# power.net
KiCad netlist of a schematic drawn in Altium Designer
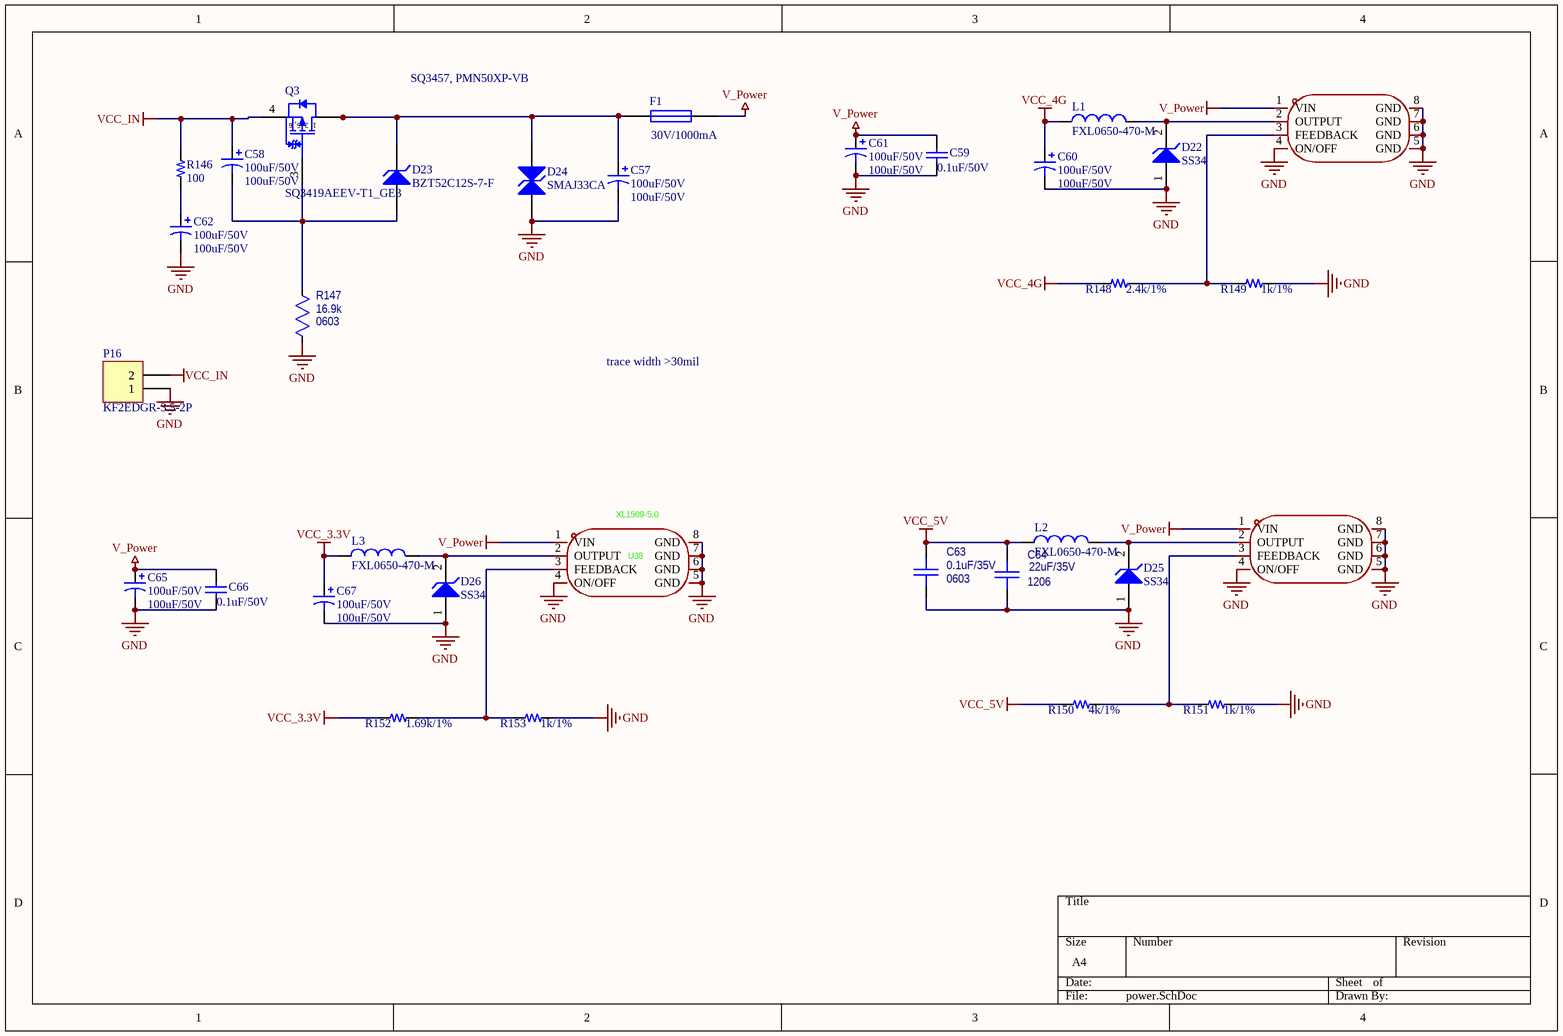
[diagram p0: power.SchDoc]

(export (version "E")
  (design (tool "Eeschema 10.0.6"))
  (components
    (comp (ref "C57")
      (value "100uF/50V")
      (footprint "CAP-SMD_BD6.3-L6.5-W6.5-LS7.0-FD:CAP-SMD_BD6.3-L6.5-W6.5-LS7.0-FD")
      (description "Polarized Capacitor (Surface Mount)")
      (fields (field (name "ALTIUM_VALUE") "100uF/50V"))
      (libsource (lib "Miscellaneous Devices") (part "Cap Pol3"))
    )
    (comp (ref "C58")
      (value "100uF/50V")
      (footprint "CAP-SMD_BD6.3-L6.5-W6.5-LS7.0-FD:CAP-SMD_BD6.3-L6.5-W6.5-LS7.0-FD")
      (description "Polarized Capacitor (Surface Mount)")
      (fields (field (name "ALTIUM_VALUE") "100uF/50V"))
      (libsource (lib "Miscellaneous Devices") (part "Cap Pol3"))
    )
    (comp (ref "C59")
      (value "0.1uF/50V")
      (footprint "0603C")
      (description "Capacitor")
      (libsource (lib "Miscellaneous Devices") (part "Cap"))
    )
    (comp (ref "C60")
      (value "100uF/50V")
      (footprint "CAP-SMD_BD6.3-L6.5-W6.5-LS7.0-FD:CAP-SMD_BD6.3-L6.5-W6.5-LS7.0-FD")
      (description "Polarized Capacitor (Surface Mount)")
      (fields (field (name "ALTIUM_VALUE") "100uF/50V"))
      (libsource (lib "Miscellaneous Devices") (part "Cap Pol3"))
    )
    (comp (ref "C61")
      (value "100uF/50V")
      (footprint "CAP-SMD_BD6.3-L6.5-W6.5-LS7.0-FD:CAP-SMD_BD6.3-L6.5-W6.5-LS7.0-FD")
      (description "Polarized Capacitor (Surface Mount)")
      (fields (field (name "ALTIUM_VALUE") "100uF/50V"))
      (libsource (lib "Miscellaneous Devices") (part "Cap Pol3"))
    )
    (comp (ref "C62")
      (value "100uF/50V")
      (footprint "CAP-SMD_BD6.3-L6.5-W6.5-LS7.0-FD:CAP-SMD_BD6.3-L6.5-W6.5-LS7.0-FD")
      (description "Polarized Capacitor (Surface Mount)")
      (fields (field (name "ALTIUM_VALUE") "100uF/50V"))
      (libsource (lib "Miscellaneous Devices") (part "Cap Pol3"))
    )
    (comp (ref "C63")
      (value "0.1uF/35V")
      (footprint "CAPC3216X156N_1206")
      (fields (field (name "PARTNUMBER") "GRM31CR61E476ME44L") (field (name "PACKAGE") "0603"))
      (libsource (lib "Karl") (part "Capacitor_1206"))
    )
    (comp (ref "C64")
      (value "22uF/35V")
      (footprint "CAPC3216X156N_1206")
      (fields (field (name "PARTNUMBER") "GRM31CR61E476ME44L") (field (name "PACKAGE") "1206"))
      (libsource (lib "Karl") (part "Capacitor_1206"))
    )
    (comp (ref "C65")
      (value "100uF/50V")
      (footprint "CAP-SMD_BD6.3-L6.5-W6.5-LS7.0-FD:CAP-SMD_BD6.3-L6.5-W6.5-LS7.0-FD")
      (description "Polarized Capacitor (Surface Mount)")
      (fields (field (name "ALTIUM_VALUE") "100uF/50V"))
      (libsource (lib "Miscellaneous Devices") (part "Cap Pol3"))
    )
    (comp (ref "C66")
      (value "0.1uF/50V")
      (footprint "0603C")
      (description "Capacitor")
      (libsource (lib "Miscellaneous Devices") (part "Cap"))
    )
    (comp (ref "C67")
      (value "100uF/50V")
      (footprint "CAP-SMD_BD6.3-L6.5-W6.5-LS7.0-FD:CAP-SMD_BD6.3-L6.5-W6.5-LS7.0-FD")
      (description "Polarized Capacitor (Surface Mount)")
      (fields (field (name "ALTIUM_VALUE") "100uF/50V"))
      (libsource (lib "Miscellaneous Devices") (part "Cap Pol3"))
    )
    (comp (ref "D22")
      (value "SS34")
      (footprint "SMA")
      (description "Schottky Barrier Rectifier, 40 V, 2-Pin SMA-FL, Pb-Free, Tape and Reel")
      (fields (field (name "PARTNUMBER") "B540C-13-F"))
      (libsource (lib "Bogen") (part "FSV340AF"))
    )
    (comp (ref "D23")
      (value "BZT52C12S-7-F")
      (footprint "DIOD-SOD323-2_V")
      (fields (field (name "PARTNUMBER") "BZT52C12S"))
      (libsource (lib "Bogen") (part "BZT52C12S-7-F"))
    )
    (comp (ref "D24")
      (value "SMAJ33CA")
      (footprint "LFUS-DO-214AC-A-2_N")
      (libsource (lib "Bogen") (part "SMAJ12CA"))
    )
    (comp (ref "D25")
      (value "SS34")
      (footprint "SMA")
      (description "Schottky Barrier Rectifier, 40 V, 2-Pin SMA-FL, Pb-Free, Tape and Reel")
      (fields (field (name "PARTNUMBER") "B540C-13-F"))
      (libsource (lib "Bogen") (part "FSV340AF"))
    )
    (comp (ref "D26")
      (value "SS34")
      (footprint "SMA")
      (description "Schottky Barrier Rectifier, 40 V, 2-Pin SMA-FL, Pb-Free, Tape and Reel")
      (fields (field (name "PARTNUMBER") "B540C-13-F"))
      (libsource (lib "Bogen") (part "FSV340AF"))
    )
    (comp (ref "F1")
      (value "30V/1000mA")
      (footprint "RESC3216X070N_1206")
      (fields (field (name "PARTNUMBER") "BSMD1206-050-30V"))
      (libsource (lib "Miscellaneous Devices") (part "Fuse 1"))
    )
    (comp (ref "L1")
      (value "FXL0650-470-M")
      (footprint "PULS-BDCD00252012_V")
      (fields (field (name "PARTNUMBER") "BDCD002520122R2MS1"))
      (libsource (lib "Bogen") (part "BDCD002520122R2MS1"))
    )
    (comp (ref "L2")
      (value "FXL0650-470-M")
      (footprint "PULS-BDCD00252012_V")
      (fields (field (name "PARTNUMBER") "BDCD002520122R2MS1"))
      (libsource (lib "Bogen") (part "BDCD002520122R2MS1"))
    )
    (comp (ref "L3")
      (value "FXL0650-470-M")
      (footprint "PULS-BDCD00252012_V")
      (fields (field (name "PARTNUMBER") "BDCD002520122R2MS1"))
      (libsource (lib "Bogen") (part "BDCD002520122R2MS1"))
    )
    (comp (ref "P16")
      (value "KF2EDGR-3.5-2P")
      (footprint "CONN-TH_P3.50_KF2EDGR-3.5-2P:CONN-TH_P3.50_KF2EDGR-3.5-2P")
      (description "Header, 2-Pin")
      (libsource (lib "Miscellaneous Connectors") (part "Header 2"))
    )
    (comp (ref "Q3")
      (value "SQ3419AEEV-T1_GE3")
      (footprint "VISH-TSOP-6_V")
      (fields (field (name "PARTNUMBER") "PMN50XP-VB"))
      (libsource (lib "Bogen") (part "SQ3419AEEV-T1_GE3"))
    )
    (comp (ref "R146")
      (value "100")
      (footprint "RESC1608X055N_0603")
      (fields (field (name "PARTNUMBER") "RC0603FR-071KL"))
      (libsource (lib "JRJ_1") (part "R"))
    )
    (comp (ref "R147")
      (value "16.9k")
      (footprint "RESC1608X055N_0603")
      (fields
        (field (name "PARTNUMBER") "FRC0603F1692TS")
        (field (name "PACKAGE") "0603")
        (field (name "Comment") "16.9k/1%")
      )
      (libsource (lib "Karl") (part "Resistor_0603"))
    )
    (comp (ref "R148")
      (value "2.4k/1%")
      (footprint "RESC1608X055N_0603")
      (fields (field (name "PARTNUMBER") "RC0603FR-071KL"))
      (libsource (lib "JRJ_1") (part "R"))
    )
    (comp (ref "R149")
      (value "1k/1%")
      (footprint "RESC1608X055N_0603")
      (fields (field (name "PARTNUMBER") "RC0603FR-071KL"))
      (libsource (lib "JRJ_1") (part "R"))
    )
    (comp (ref "R150")
      (value "4k/1%")
      (footprint "RESC1608X055N_0603")
      (fields (field (name "PARTNUMBER") "RC0603FR-071KL"))
      (libsource (lib "JRJ_1") (part "R"))
    )
    (comp (ref "R151")
      (value "1k/1%")
      (footprint "RESC1608X055N_0603")
      (fields (field (name "PARTNUMBER") "RC0603FR-071KL"))
      (libsource (lib "JRJ_1") (part "R"))
    )
    (comp (ref "R152")
      (value "1.69k/1%")
      (footprint "RESC1608X055N_0603")
      (fields (field (name "PARTNUMBER") "RC0603FR-071KL"))
      (libsource (lib "JRJ_1") (part "R"))
    )
    (comp (ref "R153")
      (value "1k/1%")
      (footprint "RESC1608X055N_0603")
      (fields (field (name "PARTNUMBER") "RC0603FR-071KL"))
      (libsource (lib "JRJ_1") (part "R"))
    )
    (comp (ref "U36")
      (value "XL1509-5.0")
      (footprint "so-8")
      (libsource (lib "altium-import") (part "root_0_XL1509-5.0_"))
    )
    (comp (ref "U37")
      (value "XL1509-5.0")
      (footprint "so-8")
      (libsource (lib "altium-import") (part "root_0_XL1509-5.0_"))
    )
    (comp (ref "U38")
      (value "XL1509-5.0")
      (footprint "so-8")
      (libsource (lib "altium-import") (part "root_0_XL1509-5.0_"))
    )
  )
  (nets
    (net (code "1") (name "GND") (class "Default")
      (node (ref "C57") (pin "2") (pinfunction "2_2") (pintype "passive"))
      (node (ref "C59") (pin "1") (pinfunction "1_1") (pintype "passive"))
      (node (ref "C60") (pin "2") (pinfunction "2_2") (pintype "passive"))
      (node (ref "C61") (pin "2") (pinfunction "2_2") (pintype "passive"))
      (node (ref "C62") (pin "2") (pinfunction "2_2") (pintype "passive"))
      (node (ref "C63") (pin "2") (pinfunction "2_2") (pintype "passive"))
      (node (ref "C64") (pin "2") (pinfunction "2_2") (pintype "passive"))
      (node (ref "C65") (pin "2") (pinfunction "2_2") (pintype "passive"))
      (node (ref "C66") (pin "1") (pinfunction "1_1") (pintype "passive"))
      (node (ref "C67") (pin "2") (pinfunction "2_2") (pintype "passive"))
      (node (ref "D22") (pin "1") (pinfunction "A_1") (pintype "passive"))
      (node (ref "D24") (pin "1") (pinfunction "A_1") (pintype "passive"))
      (node (ref "D25") (pin "1") (pinfunction "A_1") (pintype "passive"))
      (node (ref "D26") (pin "1") (pinfunction "A_1") (pintype "passive"))
      (node (ref "P16") (pin "1") (pinfunction "1_1") (pintype "passive"))
      (node (ref "R147") (pin "1") (pinfunction "1_1") (pintype "passive"))
      (node (ref "R149") (pin "1") (pintype "passive"))
      (node (ref "R151") (pin "1") (pintype "passive"))
      (node (ref "R153") (pin "1") (pintype "passive"))
      (node (ref "U36") (pin "4") (pinfunction "ON/OFF_4") (pintype "passive"))
      (node (ref "U36") (pin "5") (pinfunction "GND_5") (pintype "passive"))
      (node (ref "U36") (pin "6") (pinfunction "GND_6") (pintype "passive"))
      (node (ref "U36") (pin "7") (pinfunction "GND_7") (pintype "passive"))
      (node (ref "U36") (pin "8") (pinfunction "GND_8") (pintype "passive"))
      (node (ref "U37") (pin "4") (pinfunction "ON/OFF_4") (pintype "passive"))
      (node (ref "U37") (pin "5") (pinfunction "GND_5") (pintype "passive"))
      (node (ref "U37") (pin "6") (pinfunction "GND_6") (pintype "passive"))
      (node (ref "U37") (pin "7") (pinfunction "GND_7") (pintype "passive"))
      (node (ref "U37") (pin "8") (pinfunction "GND_8") (pintype "passive"))
      (node (ref "U38") (pin "4") (pinfunction "ON/OFF_4") (pintype "passive"))
      (node (ref "U38") (pin "5") (pinfunction "GND_5") (pintype "passive"))
      (node (ref "U38") (pin "6") (pinfunction "GND_6") (pintype "passive"))
      (node (ref "U38") (pin "7") (pinfunction "GND_7") (pintype "passive"))
      (node (ref "U38") (pin "8") (pinfunction "GND_8") (pintype "passive"))
    )
    (net (code "2") (name "Net-(C62-Pad1)") (class "Default")
      (node (ref "C62") (pin "1") (pinfunction "1_1") (pintype "passive"))
      (node (ref "R146") (pin "2") (pintype "passive"))
    )
    (net (code "3") (name "Net-(D22-K)") (class "Default")
      (node (ref "D22") (pin "2") (pinfunction "K_2") (pintype "passive"))
      (node (ref "L1") (pin "2") (pinfunction "2_2") (pintype "passive"))
      (node (ref "U36") (pin "2") (pinfunction "OUTPUT_2") (pintype "passive"))
    )
    (net (code "4") (name "Net-(D23-A)") (class "Default")
      (node (ref "C58") (pin "2") (pinfunction "2_2") (pintype "passive"))
      (node (ref "D23") (pin "1") (pinfunction "A_1") (pintype "passive"))
      (node (ref "Q3") (pin "3") (pinfunction "G_3") (pintype "passive"))
      (node (ref "R147") (pin "2") (pinfunction "2_2") (pintype "passive"))
    )
    (net (code "5") (name "Net-(D23-K)") (class "Default")
      (node (ref "C57") (pin "1") (pinfunction "1_1") (pintype "passive"))
      (node (ref "D23") (pin "2") (pinfunction "K_2") (pintype "passive"))
      (node (ref "D24") (pin "2") (pinfunction "A_2") (pintype "passive"))
      (node (ref "F1") (pin "1") (pinfunction "1_1") (pintype "passive"))
      (node (ref "Q3") (pin "1") (pinfunction "D_1") (pintype "passive"))
      (node (ref "Q3") (pin "2") (pinfunction "D_2") (pintype "passive"))
      (node (ref "Q3") (pin "5") (pinfunction "D_5") (pintype "passive"))
      (node (ref "Q3") (pin "6") (pinfunction "D_6") (pintype "passive"))
    )
    (net (code "6") (name "Net-(D25-K)") (class "Default")
      (node (ref "D25") (pin "2") (pinfunction "K_2") (pintype "passive"))
      (node (ref "L2") (pin "2") (pinfunction "2_2") (pintype "passive"))
      (node (ref "U37") (pin "2") (pinfunction "OUTPUT_2") (pintype "passive"))
    )
    (net (code "7") (name "Net-(D26-K)") (class "Default")
      (node (ref "D26") (pin "2") (pinfunction "K_2") (pintype "passive"))
      (node (ref "L3") (pin "2") (pinfunction "2_2") (pintype "passive"))
      (node (ref "U38") (pin "2") (pinfunction "OUTPUT_2") (pintype "passive"))
    )
    (net (code "8") (name "Net-(U36-FEEDBACK)") (class "Default")
      (node (ref "R148") (pin "1") (pintype "passive"))
      (node (ref "R149") (pin "2") (pintype "passive"))
      (node (ref "U36") (pin "3") (pinfunction "FEEDBACK_3") (pintype "passive"))
    )
    (net (code "9") (name "Net-(U37-FEEDBACK)") (class "Default")
      (node (ref "R150") (pin "1") (pintype "passive"))
      (node (ref "R151") (pin "2") (pintype "passive"))
      (node (ref "U37") (pin "3") (pinfunction "FEEDBACK_3") (pintype "passive"))
    )
    (net (code "10") (name "Net-(U38-FEEDBACK)") (class "Default")
      (node (ref "R152") (pin "1") (pintype "passive"))
      (node (ref "R153") (pin "2") (pintype "passive"))
      (node (ref "U38") (pin "3") (pinfunction "FEEDBACK_3") (pintype "passive"))
    )
    (net (code "11") (name "VCC_3.3V") (class "Default")
      (node (ref "C67") (pin "1") (pinfunction "1_1") (pintype "passive"))
      (node (ref "L3") (pin "1") (pinfunction "1_1") (pintype "passive"))
      (node (ref "R152") (pin "2") (pintype "passive"))
    )
    (net (code "12") (name "VCC_4G") (class "Default")
      (node (ref "C60") (pin "1") (pinfunction "1_1") (pintype "passive"))
      (node (ref "L1") (pin "1") (pinfunction "1_1") (pintype "passive"))
      (node (ref "R148") (pin "2") (pintype "passive"))
    )
    (net (code "13") (name "VCC_5V") (class "Default")
      (node (ref "C63") (pin "1") (pinfunction "1_1") (pintype "passive"))
      (node (ref "C64") (pin "1") (pinfunction "1_1") (pintype "passive"))
      (node (ref "L2") (pin "1") (pinfunction "1_1") (pintype "passive"))
      (node (ref "R150") (pin "2") (pintype "passive"))
    )
    (net (code "14") (name "VCC_IN") (class "Default")
      (node (ref "C58") (pin "1") (pinfunction "1_1") (pintype "passive"))
      (node (ref "P16") (pin "2") (pinfunction "2_2") (pintype "passive"))
      (node (ref "Q3") (pin "4") (pinfunction "S_4") (pintype "passive"))
      (node (ref "R146") (pin "1") (pintype "passive"))
    )
    (net (code "15") (name "V_Power") (class "Default")
      (node (ref "C59") (pin "2") (pinfunction "2_2") (pintype "passive"))
      (node (ref "C61") (pin "1") (pinfunction "1_1") (pintype "passive"))
      (node (ref "C65") (pin "1") (pinfunction "1_1") (pintype "passive"))
      (node (ref "C66") (pin "2") (pinfunction "2_2") (pintype "passive"))
      (node (ref "F1") (pin "2") (pinfunction "2_2") (pintype "passive"))
      (node (ref "U36") (pin "1") (pinfunction "VIN_1") (pintype "passive"))
      (node (ref "U37") (pin "1") (pinfunction "VIN_1") (pintype "passive"))
      (node (ref "U38") (pin "1") (pinfunction "VIN_1") (pintype "passive"))
    )
  )
)
